# board.net
KiCad netlist of a schematic drawn in EAGLE
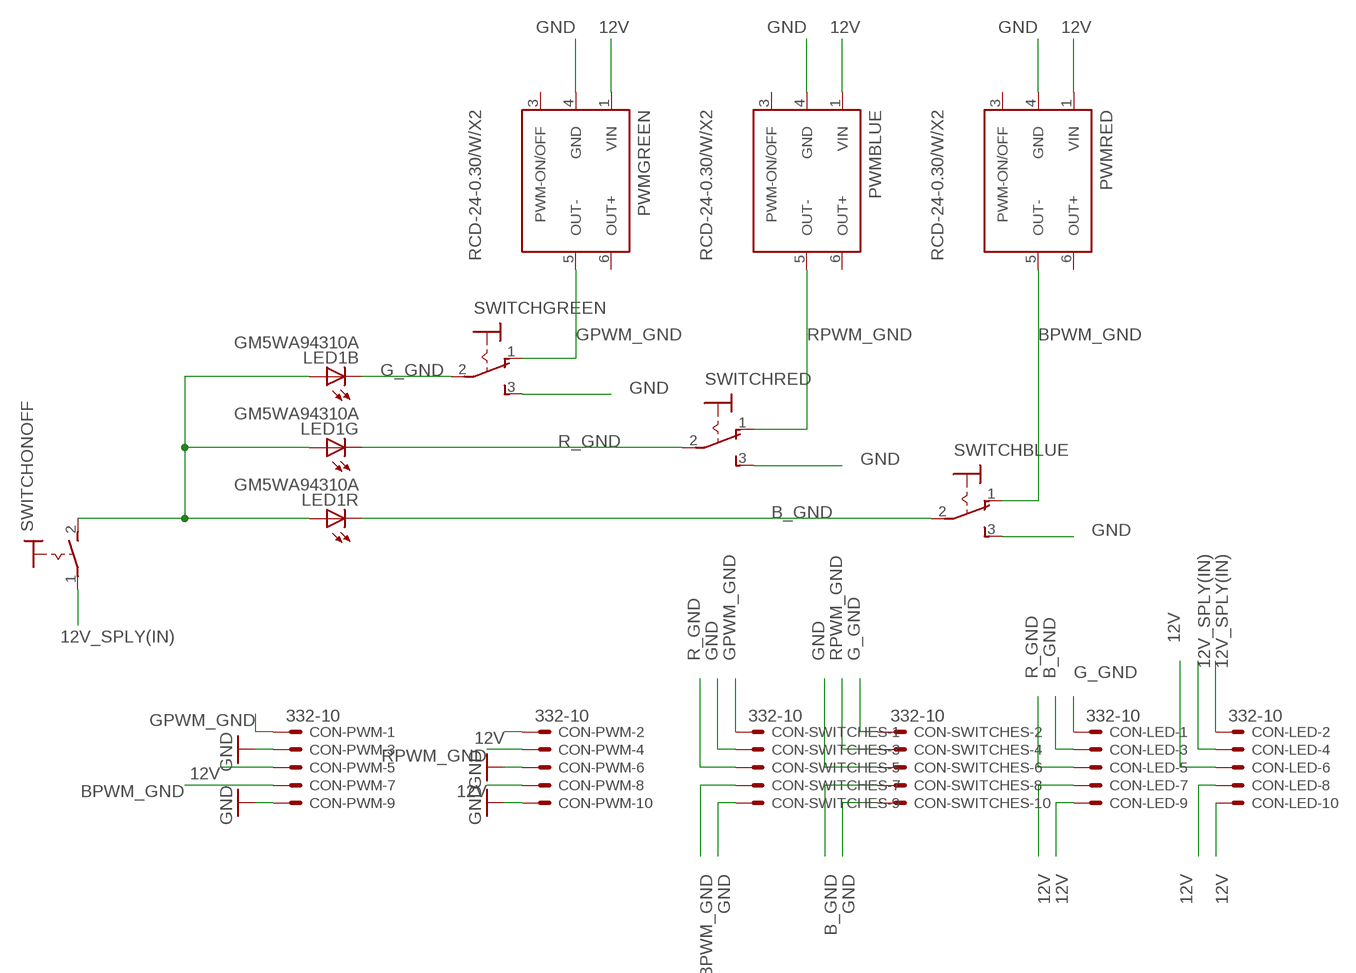
[diagram p0: schematic, sheet 1]

(export (version "E")
  (design (tool "Eeschema 10.0.6"))
  (components
    (comp (ref "CON-LED")
      (value "332-10")
      (footprint "eagle-import:332-10")
      (libsource (lib "eagle-import") (part "332-10"))
    )
    (comp (ref "CON-PWM")
      (value "332-10")
      (footprint "eagle-import:332-10")
      (libsource (lib "eagle-import") (part "332-10"))
    )
    (comp (ref "CON-SWITCHES")
      (value "332-10")
      (footprint "eagle-import:332-10")
      (libsource (lib "eagle-import") (part "332-10"))
    )
    (comp (ref "LED1")
      (value "GM5WA94310A")
      (footprint "eagle-import:GM5WA94310A")
      (libsource (lib "eagle-import") (part "GM5WA94310A"))
    )
    (comp (ref "PWMBLUE")
      (value "RCD-24-0.30/W/X2")
      (footprint "eagle-import:RCD-24_W_X2")
      (libsource (lib "eagle-import") (part "RCD-24/W/X2-0.30"))
    )
    (comp (ref "PWMGREEN")
      (value "RCD-24-0.30/W/X2")
      (footprint "eagle-import:RCD-24_W_X2")
      (libsource (lib "eagle-import") (part "RCD-24/W/X2-0.30"))
    )
    (comp (ref "PWMRED")
      (value "RCD-24-0.30/W/X2")
      (footprint "eagle-import:RCD-24_W_X2")
      (libsource (lib "eagle-import") (part "RCD-24/W/X2-0.30"))
    )
    (comp (ref "SWITCHBLUE")
      (value "M9040P")
      (footprint "eagle-import:M9040P")
      (libsource (lib "eagle-import") (part "M9040P"))
    )
    (comp (ref "SWITCHGREEN")
      (value "M9040P")
      (footprint "eagle-import:M9040P")
      (libsource (lib "eagle-import") (part "M9040P"))
    )
    (comp (ref "SWITCHONOFF")
      (value "MS243")
      (footprint "eagle-import:MS243")
      (libsource (lib "eagle-import") (part "MS243"))
    )
    (comp (ref "SWITCHRED")
      (value "M9040P")
      (footprint "eagle-import:M9040P")
      (libsource (lib "eagle-import") (part "M9040P"))
    )
  )
  (nets
    (net (code "1") (name "/12V") (class "Default")
      (node (ref "CON-LED") (pin "10") (pinfunction "S_10") (pintype "passive"))
      (node (ref "CON-LED") (pin "6") (pinfunction "S_6") (pintype "passive"))
      (node (ref "CON-LED") (pin "7") (pinfunction "S_7") (pintype "passive"))
      (node (ref "CON-LED") (pin "8") (pinfunction "S_8") (pintype "passive"))
      (node (ref "CON-LED") (pin "9") (pinfunction "S_9") (pintype "passive"))
      (node (ref "CON-PWM") (pin "2") (pinfunction "S_2") (pintype "passive"))
      (node (ref "CON-PWM") (pin "5") (pinfunction "S_5") (pintype "passive"))
      (node (ref "CON-PWM") (pin "8") (pinfunction "S_8") (pintype "passive"))
      (node (ref "LED1") (pin "1") (pinfunction "A_1") (pintype "passive"))
      (node (ref "LED1") (pin "2") (pinfunction "A_2") (pintype "passive"))
      (node (ref "LED1") (pin "3") (pinfunction "A_3") (pintype "passive"))
      (node (ref "PWMBLUE") (pin "1") (pinfunction "VIN_1") (pintype "input"))
      (node (ref "PWMGREEN") (pin "1") (pinfunction "VIN_1") (pintype "input"))
      (node (ref "PWMRED") (pin "1") (pinfunction "VIN_1") (pintype "input"))
      (node (ref "SWITCHONOFF") (pin "2") (pinfunction "S_2") (pintype "passive"))
    )
    (net (code "2") (name "/12V_SPLY(IN)") (class "Default")
      (node (ref "CON-LED") (pin "2") (pinfunction "S_2") (pintype "passive"))
      (node (ref "CON-LED") (pin "4") (pinfunction "S_4") (pintype "passive"))
      (node (ref "SWITCHONOFF") (pin "1") (pinfunction "P_1") (pintype "passive"))
    )
    (net (code "3") (name "/BPWM_GND") (class "Default")
      (node (ref "CON-PWM") (pin "7") (pinfunction "S_7") (pintype "passive"))
      (node (ref "CON-SWITCHES") (pin "7") (pinfunction "S_7") (pintype "passive"))
      (node (ref "PWMRED") (pin "5") (pinfunction "OUT-_5") (pintype "output"))
      (node (ref "SWITCHBLUE") (pin "1") (pinfunction "O_1") (pintype "passive"))
    )
    (net (code "4") (name "/B_GND") (class "Default")
      (node (ref "CON-LED") (pin "3") (pinfunction "S_3") (pintype "passive"))
      (node (ref "CON-SWITCHES") (pin "8") (pinfunction "S_8") (pintype "passive"))
      (node (ref "LED1") (pin "5") (pinfunction "C_5") (pintype "passive"))
      (node (ref "SWITCHBLUE") (pin "2") (pinfunction "P_2") (pintype "passive"))
    )
    (net (code "5") (name "/GPWM_GND") (class "Default")
      (node (ref "CON-PWM") (pin "1") (pinfunction "S_1") (pintype "passive"))
      (node (ref "CON-SWITCHES") (pin "1") (pinfunction "S_1") (pintype "passive"))
      (node (ref "PWMGREEN") (pin "5") (pinfunction "OUT-_5") (pintype "output"))
      (node (ref "SWITCHGREEN") (pin "1") (pinfunction "O_1") (pintype "passive"))
    )
    (net (code "6") (name "/G_GND") (class "Default")
      (node (ref "CON-LED") (pin "1") (pinfunction "S_1") (pintype "passive"))
      (node (ref "CON-SWITCHES") (pin "2") (pinfunction "S_2") (pintype "passive"))
      (node (ref "LED1") (pin "6") (pinfunction "C_6") (pintype "passive"))
      (node (ref "SWITCHGREEN") (pin "2") (pinfunction "P_2") (pintype "passive"))
    )
    (net (code "7") (name "/RPWM_GND") (class "Default")
      (node (ref "CON-PWM") (pin "4") (pinfunction "S_4") (pintype "passive"))
      (node (ref "CON-SWITCHES") (pin "4") (pinfunction "S_4") (pintype "passive"))
      (node (ref "PWMBLUE") (pin "5") (pinfunction "OUT-_5") (pintype "output"))
      (node (ref "SWITCHRED") (pin "1") (pinfunction "O_1") (pintype "passive"))
    )
    (net (code "8") (name "/R_GND") (class "Default")
      (node (ref "CON-LED") (pin "5") (pinfunction "S_5") (pintype "passive"))
      (node (ref "CON-SWITCHES") (pin "5") (pinfunction "S_5") (pintype "passive"))
      (node (ref "LED1") (pin "4") (pinfunction "C_4") (pintype "passive"))
      (node (ref "SWITCHRED") (pin "2") (pinfunction "P_2") (pintype "passive"))
    )
    (net (code "9") (name "GND") (class "Default")
      (node (ref "CON-PWM") (pin "10") (pinfunction "S_10") (pintype "passive"))
      (node (ref "CON-PWM") (pin "3") (pinfunction "S_3") (pintype "passive"))
      (node (ref "CON-PWM") (pin "6") (pinfunction "S_6") (pintype "passive"))
      (node (ref "CON-PWM") (pin "9") (pinfunction "S_9") (pintype "passive"))
      (node (ref "CON-SWITCHES") (pin "10") (pinfunction "S_10") (pintype "passive"))
      (node (ref "CON-SWITCHES") (pin "3") (pinfunction "S_3") (pintype "passive"))
      (node (ref "CON-SWITCHES") (pin "6") (pinfunction "S_6") (pintype "passive"))
      (node (ref "CON-SWITCHES") (pin "9") (pinfunction "S_9") (pintype "passive"))
      (node (ref "PWMBLUE") (pin "4") (pinfunction "GND_4") (pintype "power_in"))
      (node (ref "PWMGREEN") (pin "4") (pinfunction "GND_4") (pintype "power_in"))
      (node (ref "PWMRED") (pin "4") (pinfunction "GND_4") (pintype "power_in"))
      (node (ref "SWITCHBLUE") (pin "3") (pinfunction "S_3") (pintype "passive"))
      (node (ref "SWITCHGREEN") (pin "3") (pinfunction "S_3") (pintype "passive"))
      (node (ref "SWITCHRED") (pin "3") (pinfunction "S_3") (pintype "passive"))
    )
    (net (code "10") (name "unconnected-(PWMBLUE-OUT+-Pad6)") (class "Default")
      (node (ref "PWMBLUE") (pin "6") (pinfunction "OUT+_6") (pintype "output"))
    )
    (net (code "11") (name "unconnected-(PWMBLUE-PWM-ON{slash}OFF-Pad3)") (class "Default")
      (node (ref "PWMBLUE") (pin "3") (pinfunction "PWM-ON/OFF_3") (pintype "passive"))
    )
    (net (code "12") (name "unconnected-(PWMGREEN-OUT+-Pad6)") (class "Default")
      (node (ref "PWMGREEN") (pin "6") (pinfunction "OUT+_6") (pintype "output"))
    )
    (net (code "13") (name "unconnected-(PWMGREEN-PWM-ON{slash}OFF-Pad3)") (class "Default")
      (node (ref "PWMGREEN") (pin "3") (pinfunction "PWM-ON/OFF_3") (pintype "passive"))
    )
    (net (code "14") (name "unconnected-(PWMRED-OUT+-Pad6)") (class "Default")
      (node (ref "PWMRED") (pin "6") (pinfunction "OUT+_6") (pintype "output"))
    )
    (net (code "15") (name "unconnected-(PWMRED-PWM-ON{slash}OFF-Pad3)") (class "Default")
      (node (ref "PWMRED") (pin "3") (pinfunction "PWM-ON/OFF_3") (pintype "passive"))
    )
  )
)
